# main1.net
KiCad netlist of a schematic drawn in EAGLE
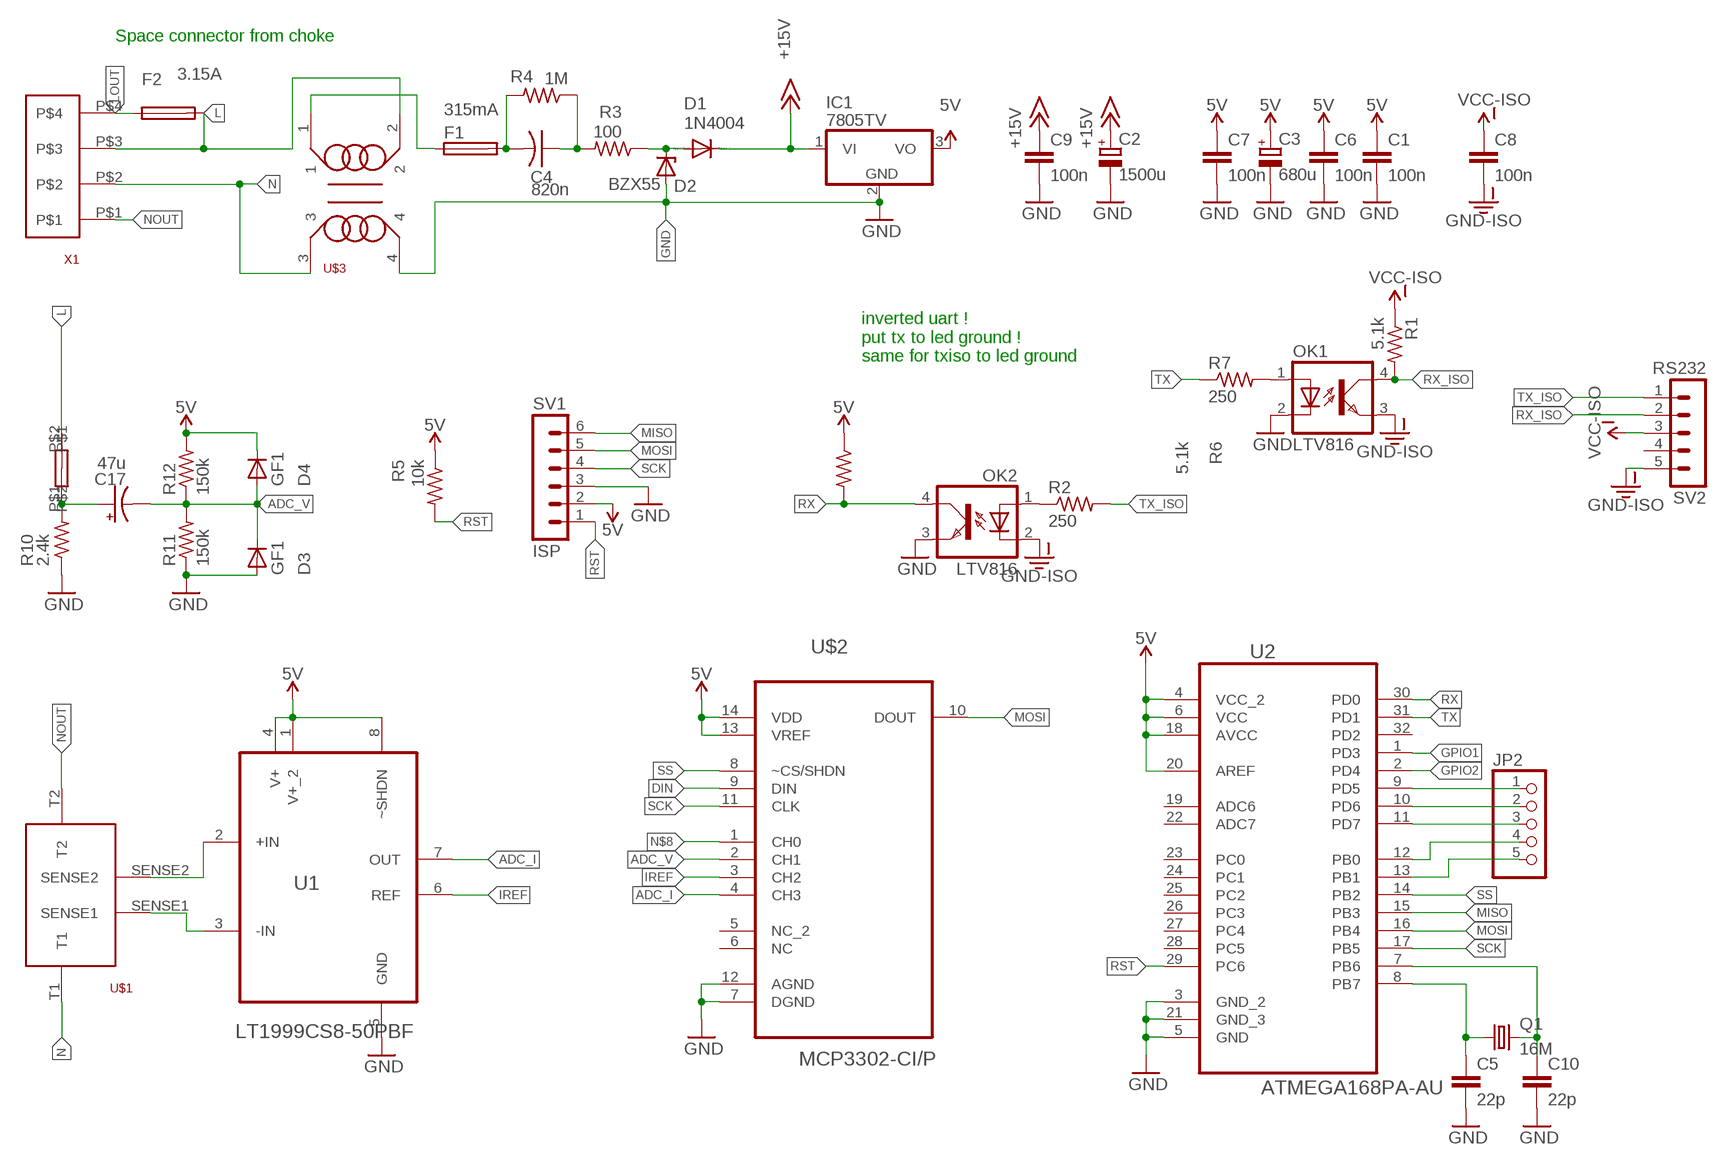
[diagram p0: schematic, sheet 1]

(export (version "E")
  (design (tool "Eeschema 10.0.6"))
  (components
    (comp (ref "C1")
      (value "100n")
      (footprint "eagle-import:C0603K")
      (libsource (lib "eagle-import") (part "C-EUC0603K"))
    )
    (comp (ref "C2")
      (value "1500u")
      (footprint "eagle-import:E5-10,5")
      (libsource (lib "eagle-import") (part "CPOL-EUE5-10.5"))
    )
    (comp (ref "C3")
      (value "680u")
      (footprint "eagle-import:E3,5-8")
      (libsource (lib "eagle-import") (part "CPOL-EUE3.5-8"))
    )
    (comp (ref "C4")
      (value "820n")
      (footprint "eagle-import:C225-087X268")
      (libsource (lib "eagle-import") (part "C-US225-087X268"))
    )
    (comp (ref "C5")
      (value "22p")
      (footprint "eagle-import:C0603")
      (libsource (lib "eagle-import") (part "C-EUC0603"))
    )
    (comp (ref "C6")
      (value "100n")
      (footprint "eagle-import:C0603K")
      (libsource (lib "eagle-import") (part "C-EUC0603K"))
    )
    (comp (ref "C7")
      (value "100n")
      (footprint "eagle-import:C0603K")
      (libsource (lib "eagle-import") (part "C-EUC0603K"))
    )
    (comp (ref "C8")
      (value "100n")
      (footprint "eagle-import:C0603")
      (libsource (lib "eagle-import") (part "C-EUC0603"))
    )
    (comp (ref "C9")
      (value "100n")
      (footprint "eagle-import:C0603K")
      (libsource (lib "eagle-import") (part "C-EUC0603K"))
    )
    (comp (ref "C10")
      (value "22p")
      (footprint "eagle-import:C0603")
      (libsource (lib "eagle-import") (part "C-EUC0603"))
    )
    (comp (ref "C17")
      (value "47u")
      (footprint "eagle-import:E5-6")
      (libsource (lib "eagle-import") (part "CPOL-USE5-6"))
    )
    (comp (ref "D1")
      (value "1N4004")
      (footprint "eagle-import:DO41-10")
      (libsource (lib "eagle-import") (part "1N4004"))
    )
    (comp (ref "D2")
      (value "BZX55")
      (footprint "eagle-import:DO35Z10")
      (libsource (lib "eagle-import") (part "BZX55"))
    )
    (comp (ref "D3")
      (value "GF1")
      (footprint "eagle-import:SMA-DO214AC")
      (libsource (lib "eagle-import") (part "GF1"))
    )
    (comp (ref "D4")
      (value "GF1")
      (footprint "eagle-import:SMA-DO214AC")
      (libsource (lib "eagle-import") (part "GF1"))
    )
    (comp (ref "F1")
      (value "315mA")
      (footprint "eagle-import:SH22,5")
      (libsource (lib "eagle-import") (part "FUSESH22,5"))
    )
    (comp (ref "F2")
      (value "3.15A")
      (footprint "eagle-import:SH22,5")
      (libsource (lib "eagle-import") (part "FUSESH22,5"))
    )
    (comp (ref "IC1")
      (value "7805TV")
      (footprint "eagle-import:TO220V")
      (libsource (lib "eagle-import") (part "78TV05"))
    )
    (comp (ref "JP2")
      (value "PINHD-1X5")
      (footprint "eagle-import:1X05")
      (libsource (lib "eagle-import") (part "PINHD-1X5"))
    )
    (comp (ref "OK1")
      (value "LTV816")
      (footprint "eagle-import:DIL04")
      (libsource (lib "eagle-import") (part "LTV816"))
    )
    (comp (ref "OK2")
      (value "LTV816")
      (footprint "eagle-import:DIL04")
      (libsource (lib "eagle-import") (part "LTV816"))
    )
    (comp (ref "Q1")
      (value "16M")
      (footprint "eagle-import:HC49U-V")
      (libsource (lib "eagle-import") (part "CRYSTALHC49U-V"))
    )
    (comp (ref "R1")
      (value "5.1k")
      (footprint "eagle-import:M0805")
      (libsource (lib "eagle-import") (part "R-US_M0805"))
    )
    (comp (ref "R2")
      (value "250")
      (footprint "eagle-import:M0805")
      (libsource (lib "eagle-import") (part "R-US_M0805"))
    )
    (comp (ref "R3")
      (value "100")
      (footprint "eagle-import:0411_15")
      (libsource (lib "eagle-import") (part "R-US_0411/15"))
    )
    (comp (ref "R4")
      (value "1M")
      (footprint "eagle-import:0617_17")
      (libsource (lib "eagle-import") (part "R-US_0617/17"))
    )
    (comp (ref "R5")
      (value "10k")
      (footprint "eagle-import:M0805")
      (libsource (lib "eagle-import") (part "R-US_M0805"))
    )
    (comp (ref "R6")
      (value "5.1k")
      (footprint "eagle-import:R0603")
      (libsource (lib "eagle-import") (part "R-US_R0603"))
    )
    (comp (ref "R7")
      (value "250")
      (footprint "eagle-import:R0603")
      (libsource (lib "eagle-import") (part "R-US_R0603"))
    )
    (comp (ref "R10")
      (value "2.4k")
      (footprint "eagle-import:0617_17")
      (libsource (lib "eagle-import") (part "R-US_0617/17"))
    )
    (comp (ref "R11")
      (value "150k")
      (footprint "eagle-import:M0805")
      (libsource (lib "eagle-import") (part "R-US_M0805"))
    )
    (comp (ref "R12")
      (value "150k")
      (footprint "eagle-import:M0805")
      (libsource (lib "eagle-import") (part "R-US_M0805"))
    )
    (comp (ref "R13")
      (value "150k180k")
      (footprint "eagle-import:RESISTOR_LONG")
      (libsource (lib "eagle-import") (part "RESISTOR_LONG"))
    )
    (comp (ref "SV1")
      (value "ISP")
      (footprint "eagle-import:MA06-1")
      (libsource (lib "eagle-import") (part "MA06-1"))
    )
    (comp (ref "SV2")
      (value "RS232")
      (footprint "eagle-import:MA05-1")
      (libsource (lib "eagle-import") (part "MA05-1"))
    )
    (comp (ref "U$1")
      (value "CSR2TTE30L0F")
      (footprint "eagle-import:CSR2TTE30L0F")
      (fields (field (name "SPICEPREFIX") "E"))
      (libsource (lib "eagle-import") (part "CSR2TTE30L0F"))
    )
    (comp (ref "U$2")
      (value "MCP3302-CI/P")
      (footprint "eagle-import:DIP254P762X533-14")
      (libsource (lib "eagle-import") (part "MCP3302-CI/P"))
    )
    (comp (ref "U$3")
      (value "B302L_CM_CHOKE")
      (footprint "eagle-import:B302L_CM_CHOKE")
      (libsource (lib "eagle-import") (part "B302L_CM_CHOKE"))
    )
    (comp (ref "U1")
      (value "LT1999CS8-50PBF")
      (footprint "eagle-import:SOIC127P600X175-8N")
      (fields (field (name "MPN") "LT1999CS8-50#PBF"))
      (libsource (lib "eagle-import") (part "LT1999CS8-50PBF"))
    )
    (comp (ref "U2")
      (value "ATMEGA168PA-AU")
      (footprint "eagle-import:QFP80P900X900X120-32N")
      (libsource (lib "eagle-import") (part "ATMEGA168PA-AU"))
    )
    (comp (ref "X1")
      (value "SCREWTERM_5MM_4WAY")
      (footprint "eagle-import:SCREWTERM_5MM_4WAY")
      (libsource (lib "eagle-import") (part "SCREWTERM_5MM_4WAY"))
    )
  )
  (nets
    (net (code "1") (name "+15V") (class "Default")
      (node (ref "C2") (pin "+") (pinfunction "+_+") (pintype "passive"))
      (node (ref "C9") (pin "1") (pinfunction "1_1") (pintype "passive"))
      (node (ref "D1") (pin "C") (pinfunction "C_C") (pintype "passive"))
      (node (ref "IC1") (pin "1") (pinfunction "VI_1") (pintype "input"))
    )
    (net (code "2") (name "5V") (class "Default")
      (node (ref "C1") (pin "1") (pinfunction "1_1") (pintype "passive"))
      (node (ref "C3") (pin "+") (pinfunction "+_+") (pintype "passive"))
      (node (ref "C6") (pin "1") (pinfunction "1_1") (pintype "passive"))
      (node (ref "C7") (pin "1") (pinfunction "1_1") (pintype "passive"))
      (node (ref "D4") (pin "K") (pinfunction "C_K") (pintype "passive"))
      (node (ref "IC1") (pin "3") (pinfunction "VO_3") (pintype "passive"))
      (node (ref "R12") (pin "2") (pinfunction "2_2") (pintype "passive"))
      (node (ref "R5") (pin "1") (pinfunction "1_1") (pintype "passive"))
      (node (ref "R6") (pin "1") (pinfunction "1_1") (pintype "passive"))
      (node (ref "SV1") (pin "2") (pinfunction "2_2") (pintype "passive"))
      (node (ref "U$2") (pin "13") (pinfunction "VREF_13") (pintype "power_in"))
      (node (ref "U$2") (pin "14") (pinfunction "VDD_14") (pintype "power_in"))
      (node (ref "U1") (pin "1") (pinfunction "V+_2_1") (pintype "power_in"))
      (node (ref "U1") (pin "4") (pinfunction "V+_4") (pintype "power_in"))
      (node (ref "U1") (pin "8") (pinfunction "~{SHDN}_8") (pintype "input"))
      (node (ref "U2") (pin "18") (pinfunction "AVCC_18") (pintype "power_in"))
      (node (ref "U2") (pin "20") (pinfunction "AREF_20") (pintype "input"))
      (node (ref "U2") (pin "4") (pinfunction "VCC_2_4") (pintype "power_in"))
      (node (ref "U2") (pin "6") (pinfunction "VCC_6") (pintype "power_in"))
    )
    (net (code "3") (name "ADC_I") (class "Default")
      (node (ref "U$2") (pin "4") (pinfunction "CH3_4") (pintype "input"))
      (node (ref "U1") (pin "7") (pinfunction "OUT_7") (pintype "output"))
    )
    (net (code "4") (name "ADC_V") (class "Default")
      (node (ref "C17") (pin "-") (pinfunction "-_-") (pintype "passive"))
      (node (ref "D3") (pin "K") (pinfunction "C_K") (pintype "passive"))
      (node (ref "D4") (pin "A") (pinfunction "A_A") (pintype "passive"))
      (node (ref "R11") (pin "2") (pinfunction "2_2") (pintype "passive"))
      (node (ref "R12") (pin "1") (pinfunction "1_1") (pintype "passive"))
      (node (ref "U$2") (pin "2") (pinfunction "CH1_2") (pintype "input"))
    )
    (net (code "5") (name "DIN") (class "Default")
      (node (ref "U$2") (pin "9") (pinfunction "DIN_9") (pintype "input"))
    )
    (net (code "6") (name "GND") (class "Default")
      (node (ref "C1") (pin "2") (pinfunction "2_2") (pintype "passive"))
      (node (ref "C10") (pin "2") (pinfunction "2_2") (pintype "passive"))
      (node (ref "C2") (pin "-") (pinfunction "-_-") (pintype "passive"))
      (node (ref "C3") (pin "-") (pinfunction "-_-") (pintype "passive"))
      (node (ref "C5") (pin "2") (pinfunction "2_2") (pintype "passive"))
      (node (ref "C6") (pin "2") (pinfunction "2_2") (pintype "passive"))
      (node (ref "C7") (pin "2") (pinfunction "2_2") (pintype "passive"))
      (node (ref "C9") (pin "2") (pinfunction "2_2") (pintype "passive"))
      (node (ref "D2") (pin "A") (pinfunction "A_A") (pintype "passive"))
      (node (ref "D3") (pin "A") (pinfunction "A_A") (pintype "passive"))
      (node (ref "IC1") (pin "2") (pinfunction "GND_2") (pintype "passive"))
      (node (ref "OK1") (pin "2") (pinfunction "C_2") (pintype "passive"))
      (node (ref "OK2") (pin "3") (pinfunction "EMIT_3") (pintype "passive"))
      (node (ref "R10") (pin "1") (pinfunction "1_1") (pintype "passive"))
      (node (ref "R11") (pin "1") (pinfunction "1_1") (pintype "passive"))
      (node (ref "SV1") (pin "3") (pinfunction "3_3") (pintype "passive"))
      (node (ref "U$2") (pin "12") (pinfunction "AGND_12") (pintype "passive"))
      (node (ref "U$2") (pin "7") (pinfunction "DGND_7") (pintype "passive"))
      (node (ref "U$3") (pin "4") (pinfunction "4_4") (pintype "bidirectional"))
      (node (ref "U1") (pin "5") (pinfunction "GND_5") (pintype "passive"))
      (node (ref "U2") (pin "21") (pinfunction "GND_3_21") (pintype "passive"))
      (node (ref "U2") (pin "3") (pinfunction "GND_2_3") (pintype "passive"))
      (node (ref "U2") (pin "5") (pinfunction "GND_5") (pintype "passive"))
    )
    (net (code "7") (name "GND-ISO") (class "Default")
      (node (ref "C8") (pin "2") (pinfunction "2_2") (pintype "passive"))
      (node (ref "OK1") (pin "3") (pinfunction "EMIT_3") (pintype "passive"))
      (node (ref "OK2") (pin "2") (pinfunction "C_2") (pintype "passive"))
      (node (ref "SV2") (pin "5") (pinfunction "5_5") (pintype "passive"))
    )
    (net (code "8") (name "GPIO1") (class "Default")
      (node (ref "U2") (pin "1") (pinfunction "PD3_1") (pintype "bidirectional"))
    )
    (net (code "9") (name "GPIO2") (class "Default")
      (node (ref "U2") (pin "2") (pinfunction "PD4_2") (pintype "bidirectional"))
    )
    (net (code "10") (name "IREF") (class "Default")
      (node (ref "U$2") (pin "3") (pinfunction "CH2_3") (pintype "input"))
      (node (ref "U1") (pin "6") (pinfunction "REF_6") (pintype "input"))
    )
    (net (code "11") (name "L") (class "Default")
      (node (ref "F2") (pin "2") (pinfunction "2_2") (pintype "passive"))
      (node (ref "R13") (pin "P$2") (pinfunction "P$2_P$2") (pintype "bidirectional"))
      (node (ref "U$3") (pin "2") (pinfunction "2_2") (pintype "bidirectional"))
      (node (ref "X1") (pin "P$3") (pinfunction "P$3_P$3") (pintype "bidirectional"))
    )
    (net (code "12") (name "LOUT") (class "Default")
      (node (ref "F2") (pin "1") (pinfunction "1_1") (pintype "passive"))
      (node (ref "X1") (pin "P$4") (pinfunction "P$4_P$4") (pintype "bidirectional"))
    )
    (net (code "13") (name "MISO") (class "Default")
      (node (ref "SV1") (pin "6") (pinfunction "6_6") (pintype "passive"))
      (node (ref "U2") (pin "15") (pinfunction "PB3_15") (pintype "bidirectional"))
    )
    (net (code "14") (name "MOSI") (class "Default")
      (node (ref "SV1") (pin "5") (pinfunction "5_5") (pintype "passive"))
      (node (ref "U$2") (pin "10") (pinfunction "DOUT_10") (pintype "output"))
      (node (ref "U2") (pin "16") (pinfunction "PB4_16") (pintype "bidirectional"))
    )
    (net (code "15") (name "N") (class "Default")
      (node (ref "U$1") (pin "T1") (pinfunction "T1_T1") (pintype "bidirectional"))
      (node (ref "U$3") (pin "3") (pinfunction "3_3") (pintype "bidirectional"))
      (node (ref "X1") (pin "P$2") (pinfunction "P$2_P$2") (pintype "bidirectional"))
    )
    (net (code "16") (name "N$8") (class "Default")
      (node (ref "U$2") (pin "1") (pinfunction "CH0_1") (pintype "input"))
    )
    (net (code "17") (name "NOUT") (class "Default")
      (node (ref "U$1") (pin "T2") (pinfunction "T2_T2") (pintype "bidirectional"))
      (node (ref "X1") (pin "P$1") (pinfunction "P$1_P$1") (pintype "bidirectional"))
    )
    (net (code "18") (name "Net-(C4-Pad1)") (class "Default")
      (node (ref "C4") (pin "1") (pinfunction "1_1") (pintype "passive"))
      (node (ref "R3") (pin "2") (pinfunction "2_2") (pintype "passive"))
      (node (ref "R4") (pin "1") (pinfunction "1_1") (pintype "passive"))
    )
    (net (code "19") (name "Net-(C4-Pad2)") (class "Default")
      (node (ref "C4") (pin "2") (pinfunction "2_2") (pintype "passive"))
      (node (ref "F1") (pin "2") (pinfunction "2_2") (pintype "passive"))
      (node (ref "R4") (pin "2") (pinfunction "2_2") (pintype "passive"))
    )
    (net (code "20") (name "Net-(C17-Pad+)") (class "Default")
      (node (ref "C17") (pin "+") (pinfunction "+_+") (pintype "passive"))
      (node (ref "R10") (pin "2") (pinfunction "2_2") (pintype "passive"))
      (node (ref "R13") (pin "P$1") (pinfunction "P$1_P$1") (pintype "bidirectional"))
    )
    (net (code "21") (name "Net-(D1-PadA)") (class "Default")
      (node (ref "D1") (pin "A") (pinfunction "A_A") (pintype "passive"))
      (node (ref "D2") (pin "C") (pinfunction "C_C") (pintype "passive"))
      (node (ref "R3") (pin "1") (pinfunction "1_1") (pintype "passive"))
    )
    (net (code "22") (name "Net-(F1-Pad1)") (class "Default")
      (node (ref "F1") (pin "1") (pinfunction "1_1") (pintype "passive"))
      (node (ref "U$3") (pin "1") (pinfunction "1_1") (pintype "bidirectional"))
    )
    (net (code "23") (name "Net-(OK1-A)") (class "Default")
      (node (ref "OK1") (pin "1") (pinfunction "A_1") (pintype "passive"))
      (node (ref "R7") (pin "2") (pinfunction "2_2") (pintype "passive"))
    )
    (net (code "24") (name "Net-(OK2-A)") (class "Default")
      (node (ref "OK2") (pin "1") (pinfunction "A_1") (pintype "passive"))
      (node (ref "R2") (pin "1") (pinfunction "1_1") (pintype "passive"))
    )
    (net (code "25") (name "Net-(U1-+IN)") (class "Default")
      (node (ref "U$1") (pin "SENSE2") (pinfunction "SENSE2_SENSE2") (pintype "bidirectional"))
      (node (ref "U1") (pin "2") (pinfunction "+IN_2") (pintype "input"))
    )
    (net (code "26") (name "Net-(U1--IN)") (class "Default")
      (node (ref "U$1") (pin "SENSE1") (pinfunction "SENSE1_SENSE1") (pintype "bidirectional"))
      (node (ref "U1") (pin "3") (pinfunction "-IN_3") (pintype "input"))
    )
    (net (code "27") (name "Net-(U2-PB0)") (class "Default")
      (node (ref "JP2") (pin "4") (pinfunction "4_4") (pintype "passive"))
      (node (ref "U2") (pin "12") (pinfunction "PB0_12") (pintype "bidirectional"))
    )
    (net (code "28") (name "Net-(U2-PB1)") (class "Default")
      (node (ref "JP2") (pin "5") (pinfunction "5_5") (pintype "passive"))
      (node (ref "U2") (pin "13") (pinfunction "PB1_13") (pintype "bidirectional"))
    )
    (net (code "29") (name "Net-(U2-PB6)") (class "Default")
      (node (ref "C10") (pin "1") (pinfunction "1_1") (pintype "passive"))
      (node (ref "Q1") (pin "2") (pinfunction "2_2") (pintype "passive"))
      (node (ref "U2") (pin "7") (pinfunction "PB6_7") (pintype "bidirectional"))
    )
    (net (code "30") (name "Net-(U2-PB7)") (class "Default")
      (node (ref "C5") (pin "1") (pinfunction "1_1") (pintype "passive"))
      (node (ref "Q1") (pin "1") (pinfunction "1_1") (pintype "passive"))
      (node (ref "U2") (pin "8") (pinfunction "PB7_8") (pintype "bidirectional"))
    )
    (net (code "31") (name "Net-(U2-PD5)") (class "Default")
      (node (ref "JP2") (pin "1") (pinfunction "1_1") (pintype "passive"))
      (node (ref "U2") (pin "9") (pinfunction "PD5_9") (pintype "bidirectional"))
    )
    (net (code "32") (name "Net-(U2-PD6)") (class "Default")
      (node (ref "JP2") (pin "2") (pinfunction "2_2") (pintype "passive"))
      (node (ref "U2") (pin "10") (pinfunction "PD6_10") (pintype "bidirectional"))
    )
    (net (code "33") (name "Net-(U2-PD7)") (class "Default")
      (node (ref "JP2") (pin "3") (pinfunction "3_3") (pintype "passive"))
      (node (ref "U2") (pin "11") (pinfunction "PD7_11") (pintype "bidirectional"))
    )
    (net (code "34") (name "RST") (class "Default")
      (node (ref "R5") (pin "2") (pinfunction "2_2") (pintype "passive"))
      (node (ref "SV1") (pin "1") (pinfunction "1_1") (pintype "passive"))
      (node (ref "U2") (pin "29") (pinfunction "PC6_29") (pintype "bidirectional"))
    )
    (net (code "35") (name "RX") (class "Default")
      (node (ref "OK2") (pin "4") (pinfunction "COL_4") (pintype "passive"))
      (node (ref "R6") (pin "2") (pinfunction "2_2") (pintype "passive"))
      (node (ref "U2") (pin "30") (pinfunction "PD0_30") (pintype "bidirectional"))
    )
    (net (code "36") (name "RX_ISO") (class "Default")
      (node (ref "OK1") (pin "4") (pinfunction "COL_4") (pintype "passive"))
      (node (ref "R1") (pin "2") (pinfunction "2_2") (pintype "passive"))
      (node (ref "SV2") (pin "2") (pinfunction "2_2") (pintype "passive"))
    )
    (net (code "37") (name "SCK") (class "Default")
      (node (ref "SV1") (pin "4") (pinfunction "4_4") (pintype "passive"))
      (node (ref "U$2") (pin "11") (pinfunction "CLK_11") (pintype "input"))
      (node (ref "U2") (pin "17") (pinfunction "PB5_17") (pintype "bidirectional"))
    )
    (net (code "38") (name "SS") (class "Default")
      (node (ref "U$2") (pin "8") (pinfunction "~{CS/SHDN}_8") (pintype "input"))
      (node (ref "U2") (pin "14") (pinfunction "PB2_14") (pintype "bidirectional"))
    )
    (net (code "39") (name "TX") (class "Default")
      (node (ref "R7") (pin "1") (pinfunction "1_1") (pintype "passive"))
      (node (ref "U2") (pin "31") (pinfunction "PD1_31") (pintype "bidirectional"))
    )
    (net (code "40") (name "TX_ISO") (class "Default")
      (node (ref "R2") (pin "2") (pinfunction "2_2") (pintype "passive"))
      (node (ref "SV2") (pin "1") (pinfunction "1_1") (pintype "passive"))
    )
    (net (code "41") (name "VCC-ISO") (class "Default")
      (node (ref "C8") (pin "1") (pinfunction "1_1") (pintype "passive"))
      (node (ref "R1") (pin "1") (pinfunction "1_1") (pintype "passive"))
      (node (ref "SV2") (pin "3") (pinfunction "3_3") (pintype "passive"))
    )
    (net (code "42") (name "unconnected-(SV2-Pad4)") (class "Default")
      (node (ref "SV2") (pin "4") (pinfunction "4_4") (pintype "passive"))
    )
    (net (code "43") (name "unconnected-(U$2-NC-Pad6)") (class "Default")
      (node (ref "U$2") (pin "6") (pinfunction "NC_6") (pintype "no_connect"))
    )
    (net (code "44") (name "unconnected-(U$2-NC_2-Pad5)") (class "Default")
      (node (ref "U$2") (pin "5") (pinfunction "NC_2_5") (pintype "no_connect"))
    )
    (net (code "45") (name "unconnected-(U2-ADC6-Pad19)") (class "Default")
      (node (ref "U2") (pin "19") (pinfunction "ADC6_19") (pintype "input"))
    )
    (net (code "46") (name "unconnected-(U2-ADC7-Pad22)") (class "Default")
      (node (ref "U2") (pin "22") (pinfunction "ADC7_22") (pintype "input"))
    )
    (net (code "47") (name "unconnected-(U2-PC0-Pad23)") (class "Default")
      (node (ref "U2") (pin "23") (pinfunction "PC0_23") (pintype "bidirectional"))
    )
    (net (code "48") (name "unconnected-(U2-PC1-Pad24)") (class "Default")
      (node (ref "U2") (pin "24") (pinfunction "PC1_24") (pintype "bidirectional"))
    )
    (net (code "49") (name "unconnected-(U2-PC2-Pad25)") (class "Default")
      (node (ref "U2") (pin "25") (pinfunction "PC2_25") (pintype "bidirectional"))
    )
    (net (code "50") (name "unconnected-(U2-PC3-Pad26)") (class "Default")
      (node (ref "U2") (pin "26") (pinfunction "PC3_26") (pintype "bidirectional"))
    )
    (net (code "51") (name "unconnected-(U2-PC4-Pad27)") (class "Default")
      (node (ref "U2") (pin "27") (pinfunction "PC4_27") (pintype "bidirectional"))
    )
    (net (code "52") (name "unconnected-(U2-PC5-Pad28)") (class "Default")
      (node (ref "U2") (pin "28") (pinfunction "PC5_28") (pintype "bidirectional"))
    )
    (net (code "53") (name "unconnected-(U2-PD2-Pad32)") (class "Default")
      (node (ref "U2") (pin "32") (pinfunction "PD2_32") (pintype "bidirectional"))
    )
  )
)
